# VelcheckPSI_G2.net
KiCad netlist of a schematic drawn in EAGLE
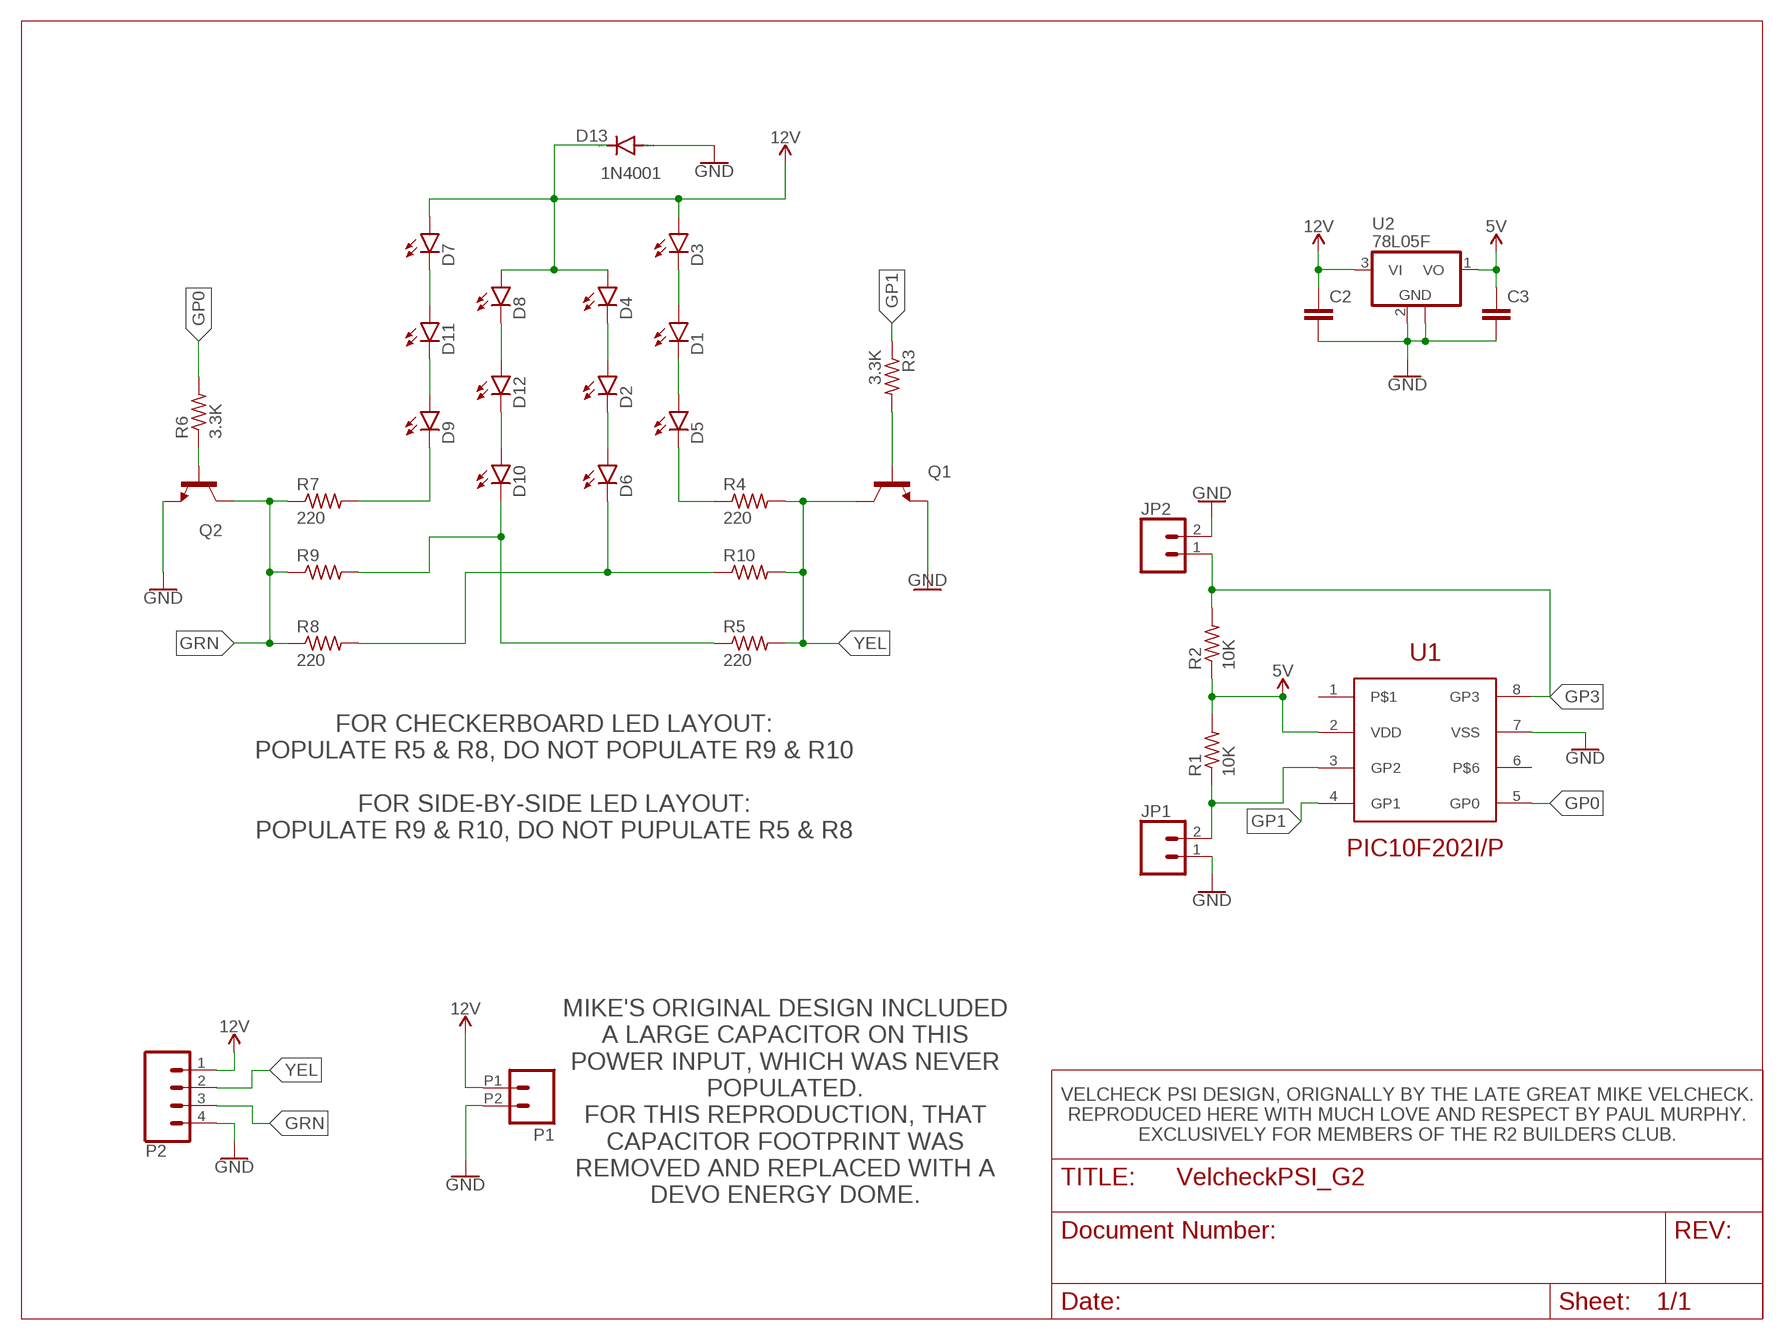
[diagram p0: schematic, sheet 1]

(export (version "E")
  (design (tool "Eeschema 10.0.6"))
  (components
    (comp (ref "C2")
      (value "C-EUC0805")
      (footprint "eagle-import:C0805")
      (libsource (lib "eagle-import") (part "C-EUC0805"))
    )
    (comp (ref "C3")
      (value "C-EUC0805")
      (footprint "eagle-import:C0805")
      (libsource (lib "eagle-import") (part "C-EUC0805"))
    )
    (comp (ref "D1")
      (value "LED5MM")
      (footprint "eagle-import:LED5MM_SLIM")
      (libsource (lib "eagle-import") (part "LED5MM"))
    )
    (comp (ref "D2")
      (value "LED5MM")
      (footprint "eagle-import:LED5MM_SLIM")
      (libsource (lib "eagle-import") (part "LED5MM"))
    )
    (comp (ref "D3")
      (value "LED5MM")
      (footprint "eagle-import:LED5MM_SLIM")
      (libsource (lib "eagle-import") (part "LED5MM"))
    )
    (comp (ref "D4")
      (value "LED5MM")
      (footprint "eagle-import:LED5MM_SLIM")
      (libsource (lib "eagle-import") (part "LED5MM"))
    )
    (comp (ref "D5")
      (value "LED5MM")
      (footprint "eagle-import:LED5MM_SLIM")
      (libsource (lib "eagle-import") (part "LED5MM"))
    )
    (comp (ref "D6")
      (value "LED5MM")
      (footprint "eagle-import:LED5MM_SLIM")
      (libsource (lib "eagle-import") (part "LED5MM"))
    )
    (comp (ref "D7")
      (value "LED5MM")
      (footprint "eagle-import:LED5MM_SLIM")
      (libsource (lib "eagle-import") (part "LED5MM"))
    )
    (comp (ref "D8")
      (value "LED5MM")
      (footprint "eagle-import:LED5MM_SLIM")
      (libsource (lib "eagle-import") (part "LED5MM"))
    )
    (comp (ref "D9")
      (value "LED5MM")
      (footprint "eagle-import:LED5MM_SLIM")
      (libsource (lib "eagle-import") (part "LED5MM"))
    )
    (comp (ref "D10")
      (value "LED5MM")
      (footprint "eagle-import:LED5MM_SLIM")
      (libsource (lib "eagle-import") (part "LED5MM"))
    )
    (comp (ref "D11")
      (value "LED5MM")
      (footprint "eagle-import:LED5MM_SLIM")
      (libsource (lib "eagle-import") (part "LED5MM"))
    )
    (comp (ref "D12")
      (value "LED5MM")
      (footprint "eagle-import:LED5MM_SLIM")
      (libsource (lib "eagle-import") (part "LED5MM"))
    )
    (comp (ref "D13")
      (value "1N4001")
      (footprint "eagle-import:DO-214AC")
      (libsource (lib "eagle-import") (part "DIODE-DO-214AC"))
    )
    (comp (ref "JP1")
      (value "CONN_02")
      (footprint "eagle-import:1X02")
      (libsource (lib "eagle-import") (part "CONN_02"))
    )
    (comp (ref "JP2")
      (value "CONN_02")
      (footprint "eagle-import:1X02")
      (libsource (lib "eagle-import") (part "CONN_02"))
    )
    (comp (ref "P1")
      (value "M022.54MM_SCREWTERM")
      (footprint "eagle-import:1X02_2.54_SCREWTERM")
      (libsource (lib "eagle-import") (part "M022.54MM_SCREWTERM"))
    )
    (comp (ref "P2")
      (value "CONN_04POLAR")
      (footprint "eagle-import:MOLEX-1X4")
      (libsource (lib "eagle-import") (part "CONN_04POLAR"))
    )
    (comp (ref "Q1")
      (value "MMBT2222ALT1-NPN-SOT23-BEC")
      (footprint "eagle-import:SOT23-BEC")
      (libsource (lib "eagle-import") (part "-NPN-SOT23-BECMMBT2222ALT1"))
    )
    (comp (ref "Q2")
      (value "MMBT2222ALT1-NPN-SOT23-BEC")
      (footprint "eagle-import:SOT23-BEC")
      (libsource (lib "eagle-import") (part "-NPN-SOT23-BECMMBT2222ALT1"))
    )
    (comp (ref "R1")
      (value "10K")
      (footprint "eagle-import:R0603")
      (libsource (lib "eagle-import") (part "R-US_R0603"))
    )
    (comp (ref "R2")
      (value "10K")
      (footprint "eagle-import:R0603")
      (libsource (lib "eagle-import") (part "R-US_R0603"))
    )
    (comp (ref "R3")
      (value "3.3K")
      (footprint "eagle-import:R0603")
      (libsource (lib "eagle-import") (part "R-US_R0603"))
    )
    (comp (ref "R4")
      (value "220")
      (footprint "eagle-import:R0603")
      (libsource (lib "eagle-import") (part "R-US_R0603"))
    )
    (comp (ref "R5")
      (value "220")
      (footprint "eagle-import:R0603")
      (libsource (lib "eagle-import") (part "R-US_R0603"))
    )
    (comp (ref "R6")
      (value "3.3K")
      (footprint "eagle-import:R0603")
      (libsource (lib "eagle-import") (part "R-US_R0603"))
    )
    (comp (ref "R7")
      (value "220")
      (footprint "eagle-import:R0603")
      (libsource (lib "eagle-import") (part "R-US_R0603"))
    )
    (comp (ref "R8")
      (value "220")
      (footprint "eagle-import:R0603")
      (libsource (lib "eagle-import") (part "R-US_R0603"))
    )
    (comp (ref "R9")
      (value "R-US_R0603")
      (footprint "eagle-import:R0603")
      (libsource (lib "eagle-import") (part "R-US_R0603"))
    )
    (comp (ref "R10")
      (value "R-US_R0603")
      (footprint "eagle-import:R0603")
      (libsource (lib "eagle-import") (part "R-US_R0603"))
    )
    (comp (ref "U1")
      (value "PIC10F202I/P")
      (footprint "eagle-import:DIP762W53P254L949H508Q8B")
      (libsource (lib "eagle-import") (part "PIC10F202I/P"))
    )
    (comp (ref "U2")
      (value "78L05F")
      (footprint "eagle-import:SOT89")
      (libsource (lib "eagle-import") (part "78LF05"))
    )
  )
  (nets
    (net (code "1") (name "5V") (class "Default")
      (node (ref "C3") (pin "1") (pinfunction "1_1") (pintype "passive"))
      (node (ref "R1") (pin "2") (pinfunction "2_2") (pintype "passive"))
      (node (ref "R2") (pin "1") (pinfunction "1_1") (pintype "passive"))
      (node (ref "U1") (pin "2") (pinfunction "VDD_2") (pintype "bidirectional"))
      (node (ref "U2") (pin "1") (pinfunction "VO_1") (pintype "passive"))
    )
    (net (code "2") (name "12V") (class "Default")
      (node (ref "C2") (pin "1") (pinfunction "1_1") (pintype "passive"))
      (node (ref "D13") (pin "C") (pinfunction "C_C") (pintype "passive"))
      (node (ref "D3") (pin "A") (pinfunction "A_A") (pintype "passive"))
      (node (ref "D4") (pin "A") (pinfunction "A_A") (pintype "passive"))
      (node (ref "D7") (pin "A") (pinfunction "A_A") (pintype "passive"))
      (node (ref "D8") (pin "A") (pinfunction "A_A") (pintype "passive"))
      (node (ref "P1") (pin "P1") (pinfunction "1_P1") (pintype "passive"))
      (node (ref "P2") (pin "1") (pinfunction "1_1") (pintype "passive"))
      (node (ref "U2") (pin "3") (pinfunction "VI_3") (pintype "input"))
    )
    (net (code "3") (name "GND") (class "Default")
      (node (ref "C2") (pin "2") (pinfunction "2_2") (pintype "passive"))
      (node (ref "C3") (pin "2") (pinfunction "2_2") (pintype "passive"))
      (node (ref "D13") (pin "A") (pinfunction "A_A") (pintype "passive"))
      (node (ref "JP1") (pin "1") (pinfunction "1_1") (pintype "passive"))
      (node (ref "JP2") (pin "2") (pinfunction "2_2") (pintype "passive"))
      (node (ref "P1") (pin "P2") (pinfunction "2_P2") (pintype "passive"))
      (node (ref "P2") (pin "4") (pinfunction "4_4") (pintype "passive"))
      (node (ref "Q1") (pin "E") (pinfunction "E_E") (pintype "passive"))
      (node (ref "Q2") (pin "E") (pinfunction "E_E") (pintype "passive"))
      (node (ref "U1") (pin "7") (pinfunction "VSS_7") (pintype "bidirectional"))
      (node (ref "U2") (pin "2") (pinfunction "GND_2") (pintype "passive"))
      (node (ref "U2") (pin "2@1") (pinfunction "GND_2@1") (pintype "passive"))
    )
    (net (code "4") (name "GP0") (class "Default")
      (node (ref "R6") (pin "2") (pinfunction "2_2") (pintype "passive"))
      (node (ref "U1") (pin "5") (pinfunction "GP0_5") (pintype "bidirectional"))
    )
    (net (code "5") (name "GP1") (class "Default")
      (node (ref "R3") (pin "1") (pinfunction "1_1") (pintype "passive"))
      (node (ref "U1") (pin "4") (pinfunction "GP1_4") (pintype "bidirectional"))
    )
    (net (code "6") (name "GP3") (class "Default")
      (node (ref "JP2") (pin "1") (pinfunction "1_1") (pintype "passive"))
      (node (ref "R2") (pin "2") (pinfunction "2_2") (pintype "passive"))
      (node (ref "U1") (pin "8") (pinfunction "GP3_8") (pintype "bidirectional"))
    )
    (net (code "7") (name "GRN") (class "Default")
      (node (ref "P2") (pin "3") (pinfunction "3_3") (pintype "passive"))
      (node (ref "Q2") (pin "C") (pinfunction "C_C") (pintype "passive"))
      (node (ref "R7") (pin "1") (pinfunction "1_1") (pintype "passive"))
      (node (ref "R8") (pin "1") (pinfunction "1_1") (pintype "passive"))
      (node (ref "R9") (pin "1") (pinfunction "1_1") (pintype "passive"))
    )
    (net (code "8") (name "Net-(D1-C)") (class "Default")
      (node (ref "D1") (pin "K") (pinfunction "C_K") (pintype "passive"))
      (node (ref "D5") (pin "A") (pinfunction "A_A") (pintype "passive"))
    )
    (net (code "9") (name "Net-(D2-C)") (class "Default")
      (node (ref "D2") (pin "K") (pinfunction "C_K") (pintype "passive"))
      (node (ref "D6") (pin "A") (pinfunction "A_A") (pintype "passive"))
    )
    (net (code "10") (name "Net-(D3-C)") (class "Default")
      (node (ref "D1") (pin "A") (pinfunction "A_A") (pintype "passive"))
      (node (ref "D3") (pin "K") (pinfunction "C_K") (pintype "passive"))
    )
    (net (code "11") (name "Net-(D4-C)") (class "Default")
      (node (ref "D2") (pin "A") (pinfunction "A_A") (pintype "passive"))
      (node (ref "D4") (pin "K") (pinfunction "C_K") (pintype "passive"))
    )
    (net (code "12") (name "Net-(D5-C)") (class "Default")
      (node (ref "D5") (pin "K") (pinfunction "C_K") (pintype "passive"))
      (node (ref "R4") (pin "1") (pinfunction "1_1") (pintype "passive"))
    )
    (net (code "13") (name "Net-(D6-C)") (class "Default")
      (node (ref "D6") (pin "K") (pinfunction "C_K") (pintype "passive"))
      (node (ref "R10") (pin "1") (pinfunction "1_1") (pintype "passive"))
      (node (ref "R8") (pin "2") (pinfunction "2_2") (pintype "passive"))
    )
    (net (code "14") (name "Net-(D7-C)") (class "Default")
      (node (ref "D11") (pin "A") (pinfunction "A_A") (pintype "passive"))
      (node (ref "D7") (pin "K") (pinfunction "C_K") (pintype "passive"))
    )
    (net (code "15") (name "Net-(D8-C)") (class "Default")
      (node (ref "D12") (pin "A") (pinfunction "A_A") (pintype "passive"))
      (node (ref "D8") (pin "K") (pinfunction "C_K") (pintype "passive"))
    )
    (net (code "16") (name "Net-(D9-C)") (class "Default")
      (node (ref "D9") (pin "K") (pinfunction "C_K") (pintype "passive"))
      (node (ref "R7") (pin "2") (pinfunction "2_2") (pintype "passive"))
    )
    (net (code "17") (name "Net-(D10-C)") (class "Default")
      (node (ref "D10") (pin "K") (pinfunction "C_K") (pintype "passive"))
      (node (ref "R5") (pin "1") (pinfunction "1_1") (pintype "passive"))
      (node (ref "R9") (pin "2") (pinfunction "2_2") (pintype "passive"))
    )
    (net (code "18") (name "Net-(D11-C)") (class "Default")
      (node (ref "D11") (pin "K") (pinfunction "C_K") (pintype "passive"))
      (node (ref "D9") (pin "A") (pinfunction "A_A") (pintype "passive"))
    )
    (net (code "19") (name "Net-(D12-C)") (class "Default")
      (node (ref "D10") (pin "A") (pinfunction "A_A") (pintype "passive"))
      (node (ref "D12") (pin "K") (pinfunction "C_K") (pintype "passive"))
    )
    (net (code "20") (name "Net-(Q1-PadB)") (class "Default")
      (node (ref "Q1") (pin "B") (pinfunction "B_B") (pintype "passive"))
      (node (ref "R3") (pin "2") (pinfunction "2_2") (pintype "passive"))
    )
    (net (code "21") (name "Net-(Q2-PadB)") (class "Default")
      (node (ref "Q2") (pin "B") (pinfunction "B_B") (pintype "passive"))
      (node (ref "R6") (pin "1") (pinfunction "1_1") (pintype "passive"))
    )
    (net (code "22") (name "Net-(U1-GP2)") (class "Default")
      (node (ref "JP1") (pin "2") (pinfunction "2_2") (pintype "passive"))
      (node (ref "R1") (pin "1") (pinfunction "1_1") (pintype "passive"))
      (node (ref "U1") (pin "3") (pinfunction "GP2_3") (pintype "bidirectional"))
    )
    (net (code "23") (name "YEL") (class "Default")
      (node (ref "P2") (pin "2") (pinfunction "2_2") (pintype "passive"))
      (node (ref "Q1") (pin "C") (pinfunction "C_C") (pintype "passive"))
      (node (ref "R10") (pin "2") (pinfunction "2_2") (pintype "passive"))
      (node (ref "R4") (pin "2") (pinfunction "2_2") (pintype "passive"))
      (node (ref "R5") (pin "2") (pinfunction "2_2") (pintype "passive"))
    )
    (net (code "24") (name "unconnected-(U1-P$1-Pad1)") (class "Default")
      (node (ref "U1") (pin "1") (pinfunction "P$1_1") (pintype "bidirectional"))
    )
    (net (code "25") (name "unconnected-(U1-P$6-Pad6)") (class "Default")
      (node (ref "U1") (pin "6") (pinfunction "P$6_6") (pintype "bidirectional"))
    )
  )
)
